# Analog.net
KiCad netlist of a schematic drawn in Altium Designer
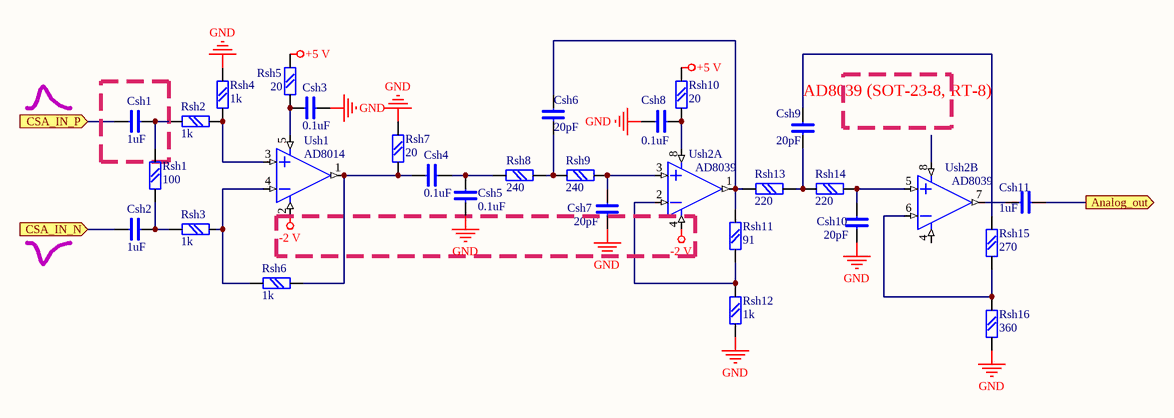
[diagram p0: Analog.SchDoc]

(export (version "E")
  (design (tool "Eeschema 10.0.6"))
  (components
    (comp (ref "Csh1") (value "1uF") (footprint "chip0603") (libsource (lib "*") (part "C")))
    (comp (ref "Csh2") (value "1uF") (footprint "chip0603") (libsource (lib "*") (part "C")))
    (comp (ref "Csh3") (value "0.1uF") (footprint "chip0603") (libsource (lib "*") (part "C")))
    (comp (ref "Csh4") (value "0.1uF") (footprint "chip0603") (libsource (lib "*") (part "C")))
    (comp (ref "Csh5") (value "0.1uF") (footprint "chip0603") (libsource (lib "*") (part "C")))
    (comp (ref "Csh6") (value "20pF") (footprint "chip0603") (libsource (lib "*") (part "C")))
    (comp (ref "Csh7") (value "20pF") (footprint "chip0603") (libsource (lib "*") (part "C")))
    (comp (ref "Csh8") (value "0.1uF") (footprint "chip0603") (libsource (lib "*") (part "C")))
    (comp (ref "Csh9") (value "20pF") (footprint "chip0603") (libsource (lib "*") (part "C")))
    (comp (ref "Csh10") (value "20pF") (footprint "chip0603") (libsource (lib "*") (part "C")))
    (comp (ref "Csh11") (value "1uF") (footprint "chip0603") (libsource (lib "*") (part "C")))
    (comp (ref "Rsh1") (value "100") (footprint "chip0603") (libsource (lib "vDevice") (part "R")))
    (comp (ref "Rsh2") (value "1k") (footprint "chip0603") (libsource (lib "vDevice") (part "R")))
    (comp (ref "Rsh3") (value "1k") (footprint "chip0603") (libsource (lib "vDevice") (part "R")))
    (comp (ref "Rsh4") (value "1k") (footprint "chip0603") (libsource (lib "vDevice") (part "R")))
    (comp (ref "Rsh5") (value "20") (footprint "chip0603") (libsource (lib "*") (part "R")))
    (comp (ref "Rsh6") (value "1k") (footprint "chip0603") (libsource (lib "vDevice") (part "R")))
    (comp (ref "Rsh7") (value "20") (footprint "chip0603") (libsource (lib "*") (part "R")))
    (comp (ref "Rsh8") (value "240") (footprint "chip0603") (libsource (lib "vDevice") (part "R")))
    (comp (ref "Rsh9") (value "240") (footprint "chip0603") (libsource (lib "vDevice") (part "R")))
    (comp (ref "Rsh10") (value "20") (footprint "chip0603") (libsource (lib "*") (part "R")))
    (comp (ref "Rsh11") (value "91") (footprint "chip0603") (libsource (lib "vDevice") (part "R")))
    (comp (ref "Rsh12") (value "1k") (footprint "chip0603") (libsource (lib "vDevice") (part "R")))
    (comp (ref "Rsh13") (value "220") (footprint "chip0603") (libsource (lib "vDevice") (part "R")))
    (comp (ref "Rsh14") (value "220") (footprint "chip0603") (libsource (lib "vDevice") (part "R")))
    (comp (ref "Rsh15") (value "270") (footprint "chip0603") (libsource (lib "vDevice") (part "R")))
    (comp (ref "Rsh16") (value "360") (footprint "chip0603") (libsource (lib "vDevice") (part "R")))
    (comp (ref "Ush1") (value "AD8014") (footprint "RT-5") (libsource (lib "vAnalog") (part "AD8005ART")))
    (comp (ref "Ush2") (value "AD8039") (footprint "SOT23-8") (libsource (lib "vAnalog") (part "AD8008")))
  )
  (nets
    (net (code "1") (name "+5 V") (class "Default")
      (node (ref "Rsh10") (pin "2") (pinfunction "2_2") (pintype "passive"))
      (node (ref "Rsh5") (pin "2") (pinfunction "2_2") (pintype "passive"))
    )
    (net (code "2") (name "-2 V") (class "Default")
      (node (ref "Ush1") (pin "2") (pinfunction "E-_2") (pintype "input"))
      (node (ref "Ush2") (pin "4") (pinfunction "E-_4") (pintype "input"))
    )
    (net (code "3") (name "/Analog_out") (class "Default")
      (node (ref "Csh11") (pin "2") (pinfunction "2_2") (pintype "passive"))
    )
    (net (code "4") (name "/CSA_IN_N") (class "Default")
      (node (ref "Csh2") (pin "1") (pinfunction "1_1") (pintype "passive"))
    )
    (net (code "5") (name "/CSA_IN_P") (class "Default")
      (node (ref "Csh1") (pin "1") (pinfunction "1_1") (pintype "passive"))
    )
    (net (code "6") (name "GND") (class "Default")
      (node (ref "Csh10") (pin "2") (pinfunction "2_2") (pintype "passive"))
      (node (ref "Csh3") (pin "2") (pinfunction "2_2") (pintype "passive"))
      (node (ref "Csh5") (pin "2") (pinfunction "2_2") (pintype "passive"))
      (node (ref "Csh7") (pin "2") (pinfunction "2_2") (pintype "passive"))
      (node (ref "Csh8") (pin "2") (pinfunction "2_2") (pintype "passive"))
      (node (ref "Rsh12") (pin "1") (pinfunction "1_1") (pintype "passive"))
      (node (ref "Rsh16") (pin "1") (pinfunction "1_1") (pintype "passive"))
      (node (ref "Rsh4") (pin "2") (pinfunction "2_2") (pintype "passive"))
      (node (ref "Rsh7") (pin "1") (pinfunction "1_1") (pintype "passive"))
    )
    (net (code "7") (name "Net-(Csh1-Pad2)") (class "Default")
      (node (ref "Csh1") (pin "2") (pinfunction "2_2") (pintype "passive"))
      (node (ref "Rsh1") (pin "2") (pinfunction "2_2") (pintype "passive"))
      (node (ref "Rsh2") (pin "1") (pinfunction "1_1") (pintype "passive"))
    )
    (net (code "8") (name "Net-(Csh2-Pad2)") (class "Default")
      (node (ref "Csh2") (pin "2") (pinfunction "2_2") (pintype "passive"))
      (node (ref "Rsh1") (pin "1") (pinfunction "1_1") (pintype "passive"))
      (node (ref "Rsh3") (pin "1") (pinfunction "1_1") (pintype "passive"))
    )
    (net (code "9") (name "Net-(Csh4-Pad1)") (class "Default")
      (node (ref "Csh4") (pin "1") (pinfunction "1_1") (pintype "passive"))
      (node (ref "Csh5") (pin "1") (pinfunction "1_1") (pintype "passive"))
      (node (ref "Rsh8") (pin "2") (pinfunction "2_2") (pintype "passive"))
    )
    (net (code "10") (name "Net-(Csh6-Pad2)") (class "Default")
      (node (ref "Csh6") (pin "2") (pinfunction "2_2") (pintype "passive"))
      (node (ref "Rsh8") (pin "1") (pinfunction "1_1") (pintype "passive"))
      (node (ref "Rsh9") (pin "1") (pinfunction "1_1") (pintype "passive"))
    )
    (net (code "11") (name "Net-(Csh9-Pad1)") (class "Default")
      (node (ref "Csh9") (pin "1") (pinfunction "1_1") (pintype "passive"))
      (node (ref "Rsh15") (pin "2") (pinfunction "2_2") (pintype "passive"))
    )
    (net (code "12") (name "Net-(Csh9-Pad2)") (class "Default")
      (node (ref "Csh9") (pin "2") (pinfunction "2_2") (pintype "passive"))
      (node (ref "Rsh13") (pin "1") (pinfunction "1_1") (pintype "passive"))
      (node (ref "Rsh14") (pin "1") (pinfunction "1_1") (pintype "passive"))
    )
    (net (code "13") (name "Net-(Ush1-+IN)") (class "Default")
      (node (ref "Rsh2") (pin "2") (pinfunction "2_2") (pintype "passive"))
      (node (ref "Rsh4") (pin "1") (pinfunction "1_1") (pintype "passive"))
      (node (ref "Ush1") (pin "3") (pinfunction "+IN_3") (pintype "input"))
    )
    (net (code "14") (name "Net-(Ush1--IN)") (class "Default")
      (node (ref "Rsh3") (pin "2") (pinfunction "2_2") (pintype "passive"))
      (node (ref "Rsh6") (pin "1") (pinfunction "1_1") (pintype "passive"))
      (node (ref "Ush1") (pin "4") (pinfunction "-IN_4") (pintype "input"))
    )
    (net (code "15") (name "Net-(Ush1-E+)") (class "Default")
      (node (ref "Csh3") (pin "1") (pinfunction "1_1") (pintype "passive"))
      (node (ref "Rsh5") (pin "1") (pinfunction "1_1") (pintype "passive"))
      (node (ref "Ush1") (pin "5") (pinfunction "E+_5") (pintype "input"))
    )
    (net (code "16") (name "Net-(Ush1-OUT)") (class "Default")
      (node (ref "Csh4") (pin "2") (pinfunction "2_2") (pintype "passive"))
      (node (ref "Rsh6") (pin "2") (pinfunction "2_2") (pintype "passive"))
      (node (ref "Rsh7") (pin "2") (pinfunction "2_2") (pintype "passive"))
      (node (ref "Ush1") (pin "1") (pinfunction "OUT_1") (pintype "output"))
    )
    (net (code "17") (name "Net-(Ush2A-+IN)") (class "Default")
      (node (ref "Csh7") (pin "1") (pinfunction "1_1") (pintype "passive"))
      (node (ref "Rsh9") (pin "2") (pinfunction "2_2") (pintype "passive"))
      (node (ref "Ush2") (pin "3") (pinfunction "+IN_3") (pintype "input"))
    )
    (net (code "18") (name "Net-(Ush2A--IN)") (class "Default")
      (node (ref "Rsh11") (pin "1") (pinfunction "1_1") (pintype "passive"))
      (node (ref "Rsh12") (pin "2") (pinfunction "2_2") (pintype "passive"))
      (node (ref "Ush2") (pin "2") (pinfunction "-IN_2") (pintype "input"))
    )
    (net (code "19") (name "Net-(Ush2A-E+)") (class "Default")
      (node (ref "Csh8") (pin "1") (pinfunction "1_1") (pintype "passive"))
      (node (ref "Rsh10") (pin "1") (pinfunction "1_1") (pintype "passive"))
      (node (ref "Ush2") (pin "8") (pinfunction "E+_8") (pintype "input"))
    )
    (net (code "20") (name "Net-(Ush2A-OUT)") (class "Default")
      (node (ref "Csh6") (pin "1") (pinfunction "1_1") (pintype "passive"))
      (node (ref "Rsh11") (pin "2") (pinfunction "2_2") (pintype "passive"))
      (node (ref "Rsh13") (pin "2") (pinfunction "2_2") (pintype "passive"))
      (node (ref "Ush2") (pin "1") (pinfunction "OUT_1") (pintype "output"))
    )
    (net (code "21") (name "Net-(Ush2B-+IN)") (class "Default")
      (node (ref "Csh10") (pin "1") (pinfunction "1_1") (pintype "passive"))
      (node (ref "Rsh14") (pin "2") (pinfunction "2_2") (pintype "passive"))
      (node (ref "Ush2") (pin "5") (pinfunction "+IN_5") (pintype "input"))
    )
    (net (code "22") (name "Net-(Ush2B--IN)") (class "Default")
      (node (ref "Rsh15") (pin "1") (pinfunction "1_1") (pintype "passive"))
      (node (ref "Rsh16") (pin "2") (pinfunction "2_2") (pintype "passive"))
      (node (ref "Ush2") (pin "6") (pinfunction "-IN_6") (pintype "input"))
    )
    (net (code "23") (name "Net-(Ush2B-OUT)") (class "Default")
      (node (ref "Csh11") (pin "1") (pinfunction "1_1") (pintype "passive"))
      (node (ref "Ush2") (pin "7") (pinfunction "OUT_7") (pintype "output"))
    )
    (net (code "24") (name "unconnected-(Ush2B-E+-Pad8)") (class "Default")
      (node (ref "Ush2") (pin "8") (pinfunction "E+_8") (pintype "input"))
    )
    (net (code "25") (name "unconnected-(Ush2B-E--Pad4)") (class "Default")
      (node (ref "Ush2") (pin "4") (pinfunction "E-_4") (pintype "input"))
    )
  )
)
